# DEVICE.net
KiCad netlist of a schematic drawn in Altium Designer
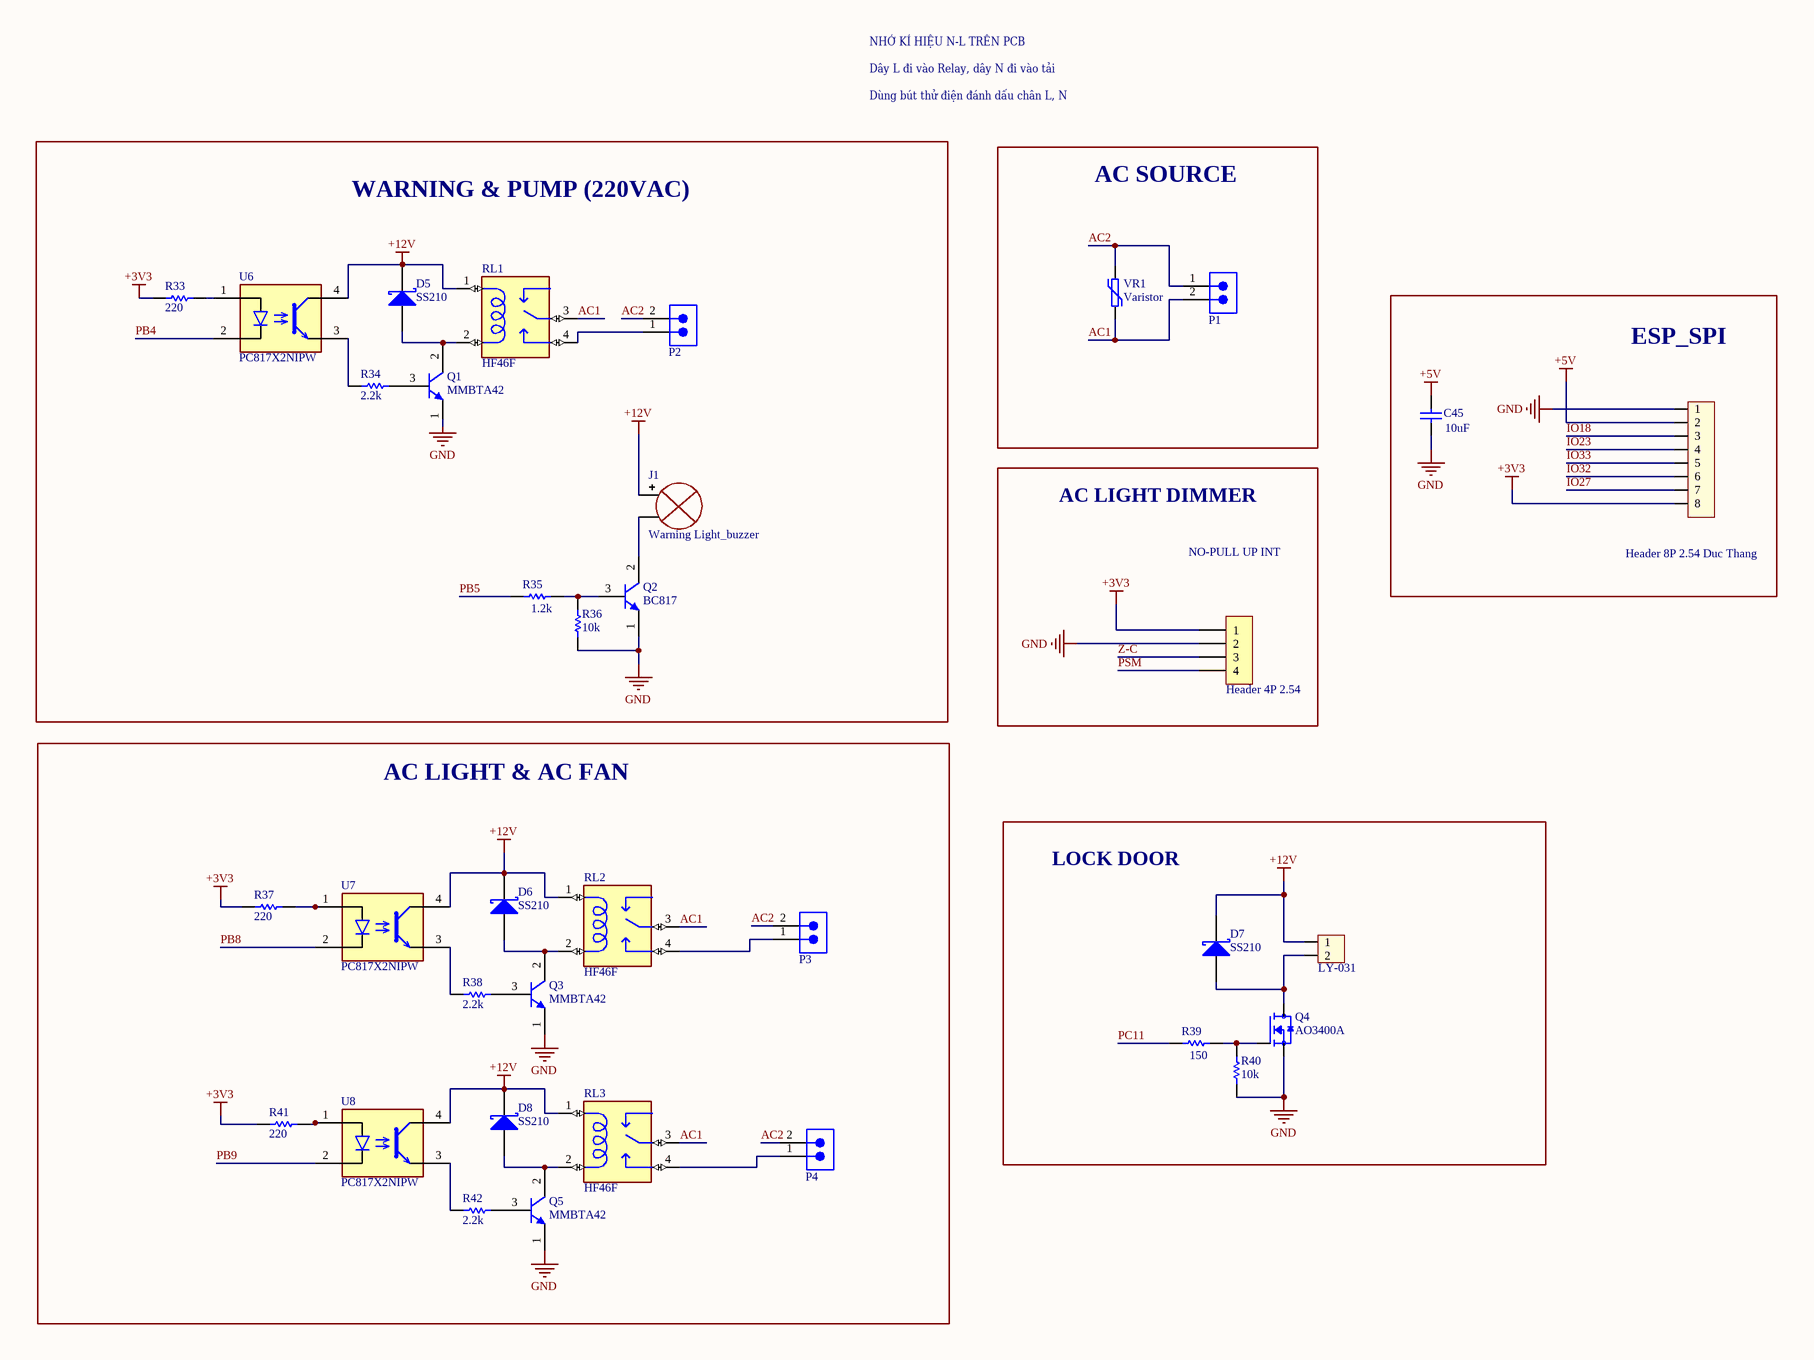
[diagram p0: DEVICE.SchDoc, left]
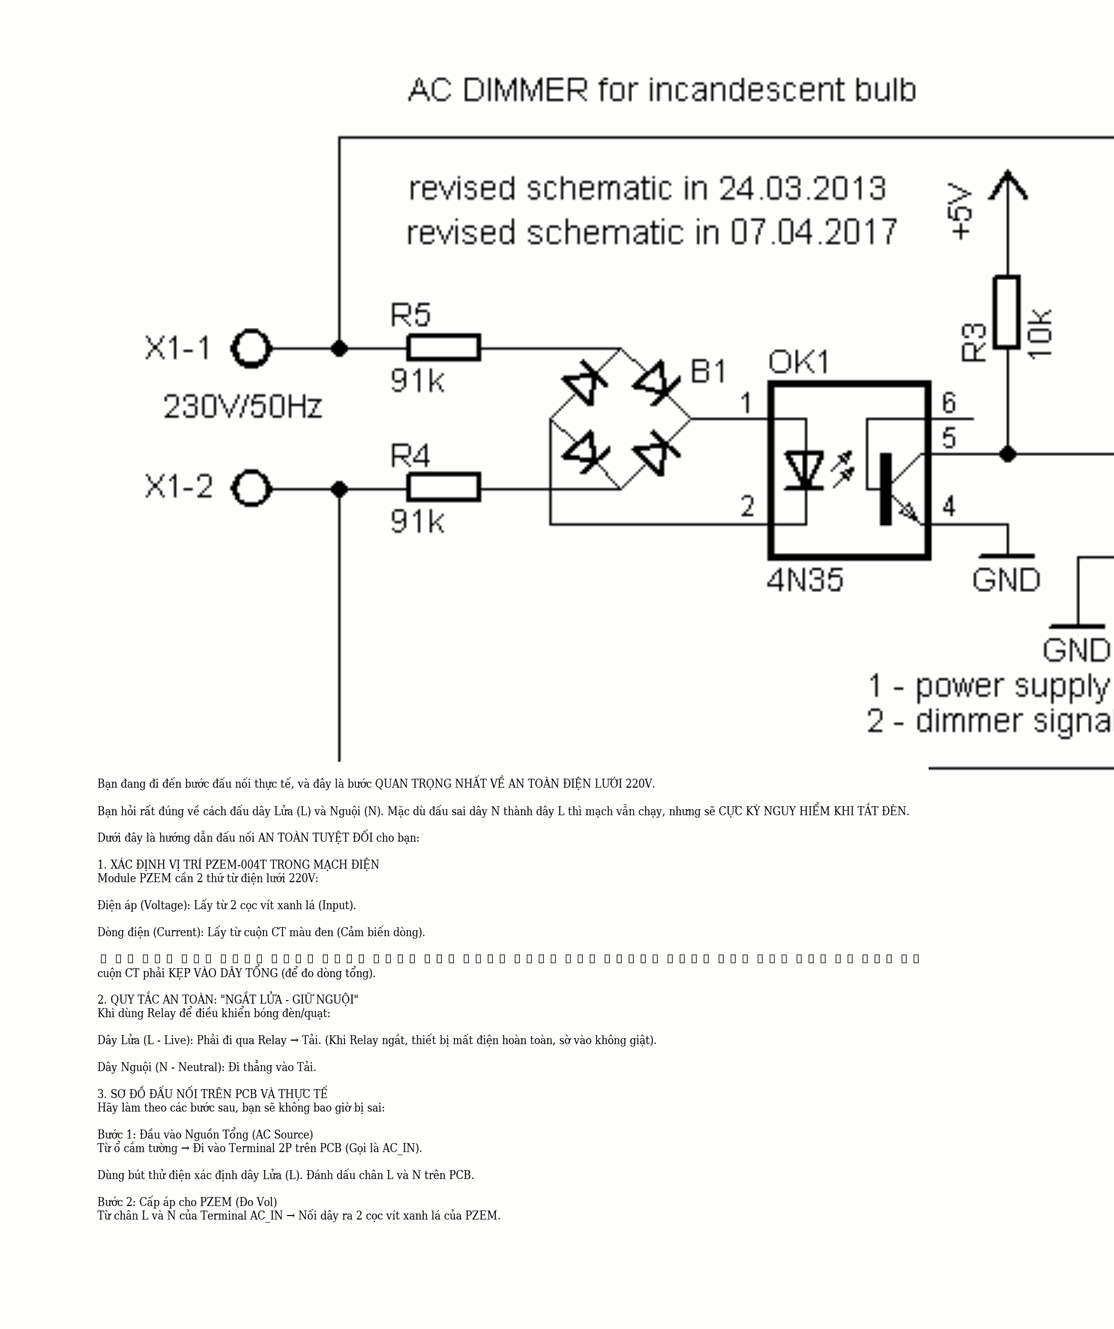
[diagram p1: DEVICE.SchDoc, middle]
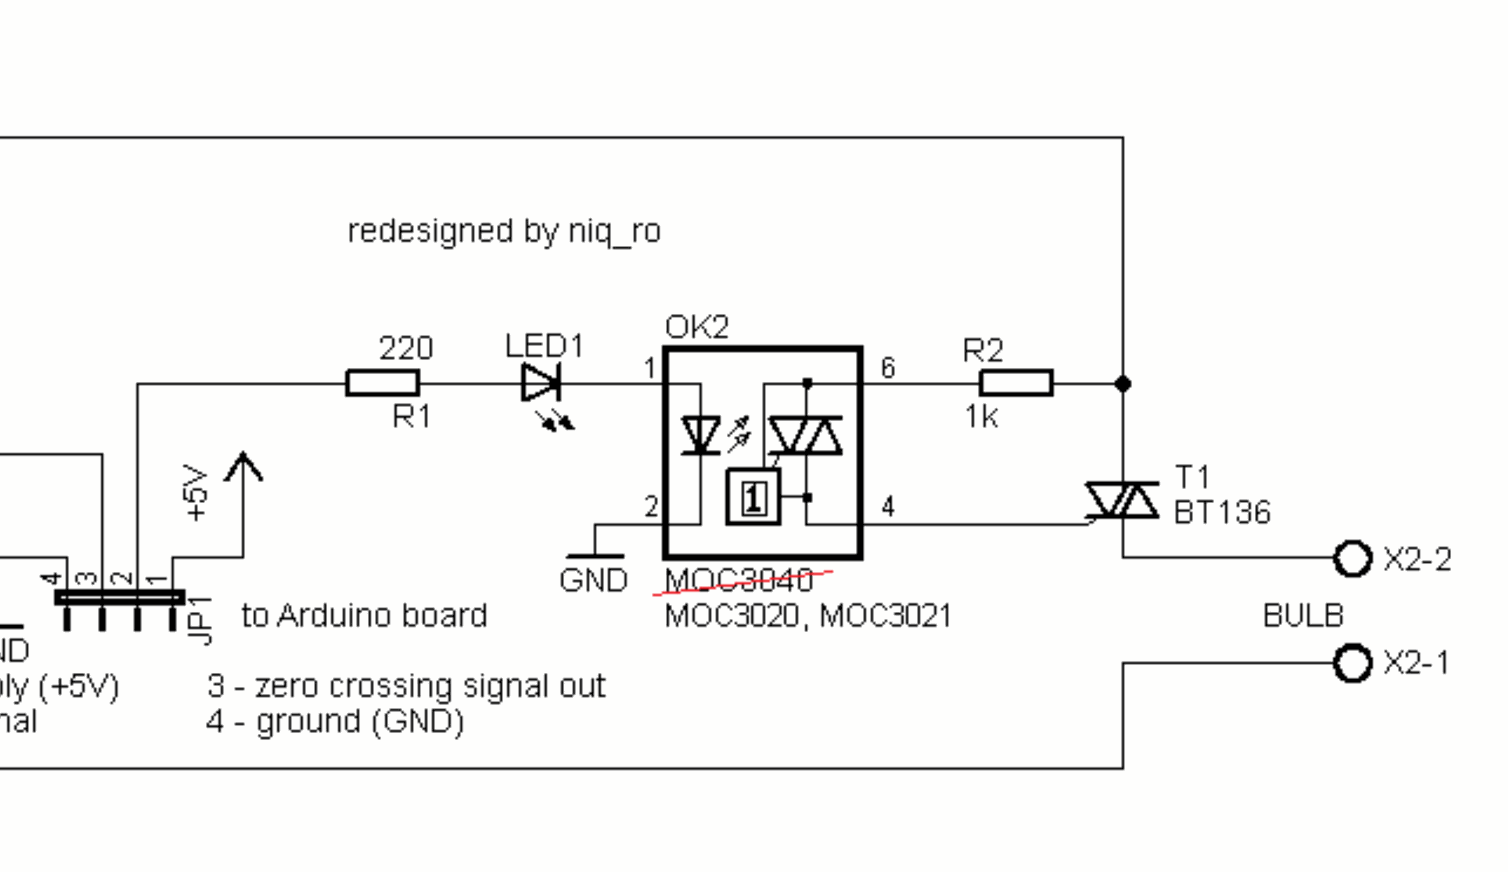
[diagram p2: DEVICE.SchDoc, right]

(export (version "E")
  (design (tool "Eeschema 10.0.6"))
  (components
    (comp (ref "C45")
      (value "10uF")
      (footprint "CAP_0603")
      (description "CAP, size 0603,10uF")
      (libsource (lib "SMIOT_Lib_Schematic") (part "01060310010"))
    )
    (comp (ref "D5")
      (value "SS210")
      (footprint "SS34")
      (description "Schottky Diode")
      (fields (field (name "PUBLISHER") "Altium Limited"))
      (libsource (lib "SMIOT_Lib_Schematic") (part "D Schottky"))
    )
    (comp (ref "D6")
      (value "SS210")
      (footprint "SS34")
      (description "Schottky Diode")
      (fields (field (name "PUBLISHER") "Altium Limited"))
      (libsource (lib "SMIOT_Lib_Schematic") (part "D Schottky"))
    )
    (comp (ref "D7")
      (value "SS210")
      (footprint "SS34")
      (description "Schottky Diode")
      (fields (field (name "PUBLISHER") "Altium Limited"))
      (libsource (lib "SMIOT_Lib_Schematic") (part "D Schottky"))
    )
    (comp (ref "D8")
      (value "SS210")
      (footprint "SS34")
      (description "Schottky Diode")
      (fields (field (name "PUBLISHER") "Altium Limited"))
      (libsource (lib "SMIOT_Lib_Schematic") (part "D Schottky"))
    )
    (comp (ref "H19")
      (value "Header 8P 2.54 Duc Thang")
      (footprint "XH2.54M-8")
      (description "Cắm")
      (libsource (lib "Header") (part "Header 8P 2.54 Duc Thang"))
    )
    (comp (ref "H20")
      (value "Header 4P 2.54")
      (footprint "XH2.54M-4")
      (description "Cắm")
      (libsource (lib "Header") (part "Header 4P 2.54 Duc Thang"))
    )
    (comp (ref "H21")
      (value "LY-031")
      (footprint "XH2.54M-2")
      (description "Cắm")
      (libsource (lib "Header") (part "Header 2P 2.54 Duc Thang"))
    )
    (comp (ref "J1")
      (value "Warning Light_buzzer")
      (footprint "PHOENIX_1935161")
      (libsource (lib "Tironzi") (part "Light_12V"))
    )
    (comp (ref "P1")
      (value "691322310002")
      (footprint "691322310002")
      (description "WR-TBL Series 322 Horizontal PCB Header, THT, pitch 3.81mm, 2p")
      (fields (field (name "MANUFACTURER") "Wurth Elektronik"))
      (libsource (lib "SMIOT_Lib_Schematic") (part "691322310002"))
    )
    (comp (ref "P2")
      (value "691322310002")
      (footprint "691322310002")
      (description "WR-TBL Series 322 Horizontal PCB Header, THT, pitch 3.81mm, 2p")
      (fields (field (name "MANUFACTURER") "Wurth Elektronik"))
      (libsource (lib "SMIOT_Lib_Schematic") (part "691322310002"))
    )
    (comp (ref "P3")
      (value "691322310002")
      (footprint "691322310002")
      (description "WR-TBL Series 322 Horizontal PCB Header, THT, pitch 3.81mm, 2p")
      (fields (field (name "MANUFACTURER") "Wurth Elektronik"))
      (libsource (lib "SMIOT_Lib_Schematic") (part "691322310002"))
    )
    (comp (ref "P4")
      (value "691322310002")
      (footprint "691322310002")
      (description "WR-TBL Series 322 Horizontal PCB Header, THT, pitch 3.81mm, 2p")
      (fields (field (name "MANUFACTURER") "Wurth Elektronik"))
      (libsource (lib "SMIOT_Lib_Schematic") (part "691322310002"))
    )
    (comp (ref "Q1")
      (value "MMBTA42")
      (footprint "SOT23B")
      (description "NPN Bipolar Transistor")
      (libsource (lib "SMIOT_Lib_Schematic") (part "BC817"))
    )
    (comp (ref "Q2")
      (value "BC817")
      (footprint "SOT23B")
      (description "NPN Bipolar Transistor")
      (libsource (lib "SMIOT_Lib_Schematic") (part "BC817"))
    )
    (comp (ref "Q3")
      (value "MMBTA42")
      (footprint "SOT23B")
      (description "NPN Bipolar Transistor")
      (libsource (lib "SMIOT_Lib_Schematic") (part "BC817"))
    )
    (comp (ref "Q4")
      (value "AO3400A")
      (footprint "SOT95P280X125-3N")
      (description "N-Channel 30 V 5.7A (Ta) 1.4W (Ta) Surface Mount SOT-23-3")
      (fields (field (name "MF") "Alpha & Omega Semiconductor"))
      (libsource (lib "AO3400A") (part "AO3400A"))
    )
    (comp (ref "Q5")
      (value "MMBTA42")
      (footprint "SOT23B")
      (description "NPN Bipolar Transistor")
      (libsource (lib "SMIOT_Lib_Schematic") (part "BC817"))
    )
    (comp (ref "R33")
      (value "220")
      (footprint "resistor_0603")
      (description "RES, 220 Ohm, size 0603, 1%")
      (libsource (lib "SMIOT_Lib_Schematic") (part "0006032211"))
    )
    (comp (ref "R34")
      (value "2.2k")
      (footprint "resistor_0603")
      (description "RES, 2.2k Ohm, size 0603, 1%")
      (libsource (lib "SMIOT_Lib_Schematic") (part "0006032221"))
    )
    (comp (ref "R35")
      (value "1.2k")
      (footprint "resistor_0603")
      (description "RES, 1.2k Ohm, size 0603, 1%")
      (libsource (lib "SMIOT_Lib_Schematic") (part "0006032221"))
    )
    (comp (ref "R36")
      (value "10k")
      (footprint "resistor_0603")
      (description "RES, 10k Ohm, size 0603, 1%")
      (libsource (lib "SMIOT_Lib_Schematic") (part "0006032221"))
    )
    (comp (ref "R37")
      (value "220")
      (footprint "resistor_0603")
      (description "RES, 220 Ohm, size 0603, 1%")
      (libsource (lib "SMIOT_Lib_Schematic") (part "0006032211"))
    )
    (comp (ref "R38")
      (value "2.2k")
      (footprint "resistor_0603")
      (description "RES, 2.2k Ohm, size 0603, 1%")
      (libsource (lib "SMIOT_Lib_Schematic") (part "0006032221"))
    )
    (comp (ref "R39")
      (value "150")
      (footprint "resistor_0603")
      (description "RES, 150 Ohm, size 0603, 1%")
      (libsource (lib "SMIOT_Lib_Schematic") (part "0006032221"))
    )
    (comp (ref "R40")
      (value "10k")
      (footprint "resistor_0603")
      (description "RES, 10k Ohm, size 0603, 1%")
      (libsource (lib "SMIOT_Lib_Schematic") (part "0006032221"))
    )
    (comp (ref "R41")
      (value "220")
      (footprint "resistor_0603")
      (description "RES, 220 Ohm, size 0603, 1%")
      (libsource (lib "SMIOT_Lib_Schematic") (part "0006032211"))
    )
    (comp (ref "R42")
      (value "2.2k")
      (footprint "resistor_0603")
      (description "RES, 2.2k Ohm, size 0603, 1%")
      (libsource (lib "SMIOT_Lib_Schematic") (part "0006032221"))
    )
    (comp (ref "RL1")
      (value "HF46F")
      (footprint "HF46F")
      (description "SeriesHF46F 12V 1 Form A 1A Gold Plated SUBMINIATURE INTERMEDIATE POWER RELAY")
      (fields (field (name "MF") "Hongfa"))
      (libsource (lib "SMIOT_Lib_Schematic") (part "HF46F"))
    )
    (comp (ref "RL2")
      (value "HF46F")
      (footprint "HF46F")
      (description "SeriesHF46F 12V 1 Form A 1A Gold Plated SUBMINIATURE INTERMEDIATE POWER RELAY")
      (fields (field (name "MF") "Hongfa"))
      (libsource (lib "SMIOT_Lib_Schematic") (part "HF46F"))
    )
    (comp (ref "RL3")
      (value "HF46F")
      (footprint "HF46F")
      (description "SeriesHF46F 12V 1 Form A 1A Gold Plated SUBMINIATURE INTERMEDIATE POWER RELAY")
      (fields (field (name "MF") "Hongfa"))
      (libsource (lib "SMIOT_Lib_Schematic") (part "HF46F"))
    )
    (comp (ref "U6")
      (value "PC817X2NIPW")
      (footprint "PC817XI_SHP")
      (libsource (lib "SMIOT_Lib_Schematic") (part "PC817X2NIPW"))
    )
    (comp (ref "U7")
      (value "PC817X2NIPW")
      (footprint "PC817XI_SHP")
      (libsource (lib "SMIOT_Lib_Schematic") (part "PC817X2NIPW"))
    )
    (comp (ref "U8")
      (value "PC817X2NIPW")
      (footprint "PC817XI_SHP")
      (libsource (lib "SMIOT_Lib_Schematic") (part "PC817X2NIPW"))
    )
    (comp (ref "VR1")
      (value "Varistor")
      (footprint "07D471K")
      (description "07D471K 470V")
      (libsource (lib "SMIOT_Lib_Schematic") (part "07D471K 470V"))
    )
  )
  (nets
    (net (code "1") (name "+3V3") (class "Default")
      (node (ref "H19") (pin "8") (pinfunction "8_8") (pintype "passive"))
      (node (ref "H20") (pin "1") (pinfunction "1_1") (pintype "passive"))
      (node (ref "R33") (pin "1") (pinfunction "1_1") (pintype "passive"))
      (node (ref "R37") (pin "1") (pinfunction "1_1") (pintype "passive"))
      (node (ref "R41") (pin "1") (pinfunction "1_1") (pintype "passive"))
    )
    (net (code "2") (name "+5V") (class "Default")
      (node (ref "C45") (pin "2") (pinfunction "2_2") (pintype "passive"))
      (node (ref "H19") (pin "2") (pinfunction "2_2") (pintype "passive"))
    )
    (net (code "3") (name "+12V") (class "Default")
      (node (ref "D5") (pin "2") (pinfunction "K_2") (pintype "passive"))
      (node (ref "D6") (pin "2") (pinfunction "K_2") (pintype "passive"))
      (node (ref "D7") (pin "2") (pinfunction "K_2") (pintype "passive"))
      (node (ref "D8") (pin "2") (pinfunction "K_2") (pintype "passive"))
      (node (ref "H21") (pin "1") (pinfunction "1_1") (pintype "passive"))
      (node (ref "J1") (pin "1") (pinfunction "+_1") (pintype "passive"))
      (node (ref "RL1") (pin "1") (pinfunction "C1_1") (pintype "bidirectional"))
      (node (ref "RL2") (pin "1") (pinfunction "C1_1") (pintype "bidirectional"))
      (node (ref "RL3") (pin "1") (pinfunction "C1_1") (pintype "bidirectional"))
      (node (ref "U6") (pin "4") (pinfunction "4_4") (pintype "passive"))
      (node (ref "U7") (pin "4") (pinfunction "4_4") (pintype "passive"))
      (node (ref "U8") (pin "4") (pinfunction "4_4") (pintype "passive"))
    )
    (net (code "4") (name "/AC1") (class "Default")
      (node (ref "P1") (pin "2") (pinfunction "2_2") (pintype "passive"))
      (node (ref "RL1") (pin "3") (pinfunction "C_3") (pintype "bidirectional"))
      (node (ref "RL2") (pin "3") (pinfunction "C_3") (pintype "bidirectional"))
      (node (ref "RL3") (pin "3") (pinfunction "C_3") (pintype "bidirectional"))
      (node (ref "VR1") (pin "2") (pinfunction "2_2") (pintype "passive"))
    )
    (net (code "5") (name "/AC2") (class "Default")
      (node (ref "P1") (pin "1") (pinfunction "1_1") (pintype "passive"))
      (node (ref "P2") (pin "2") (pinfunction "2_2") (pintype "passive"))
      (node (ref "P3") (pin "2") (pinfunction "2_2") (pintype "passive"))
      (node (ref "P4") (pin "2") (pinfunction "2_2") (pintype "passive"))
      (node (ref "VR1") (pin "1") (pinfunction "1_1") (pintype "passive"))
    )
    (net (code "6") (name "/IO18") (class "Default")
      (node (ref "H19") (pin "3") (pinfunction "3_3") (pintype "passive"))
    )
    (net (code "7") (name "/IO23") (class "Default")
      (node (ref "H19") (pin "4") (pinfunction "4_4") (pintype "passive"))
    )
    (net (code "8") (name "/IO27") (class "Default")
      (node (ref "H19") (pin "7") (pinfunction "7_7") (pintype "passive"))
    )
    (net (code "9") (name "/IO32") (class "Default")
      (node (ref "H19") (pin "6") (pinfunction "6_6") (pintype "passive"))
    )
    (net (code "10") (name "/IO33") (class "Default")
      (node (ref "H19") (pin "5") (pinfunction "5_5") (pintype "passive"))
    )
    (net (code "11") (name "/PB4") (class "Default")
      (node (ref "U6") (pin "2") (pinfunction "2_2") (pintype "passive"))
    )
    (net (code "12") (name "/PB5") (class "Default")
      (node (ref "R35") (pin "1") (pinfunction "1_1") (pintype "passive"))
    )
    (net (code "13") (name "/PB8") (class "Default")
      (node (ref "U7") (pin "2") (pinfunction "2_2") (pintype "passive"))
    )
    (net (code "14") (name "/PB9") (class "Default")
      (node (ref "U8") (pin "2") (pinfunction "2_2") (pintype "passive"))
    )
    (net (code "15") (name "/PC11") (class "Default")
      (node (ref "R39") (pin "1") (pinfunction "1_1") (pintype "passive"))
    )
    (net (code "16") (name "/PSM") (class "Default")
      (node (ref "H20") (pin "4") (pinfunction "4_4") (pintype "passive"))
    )
    (net (code "17") (name "/Z-C") (class "Default")
      (node (ref "H20") (pin "3") (pinfunction "3_3") (pintype "passive"))
    )
    (net (code "18") (name "GND") (class "Default")
      (node (ref "C45") (pin "1") (pinfunction "1_1") (pintype "passive"))
      (node (ref "H19") (pin "1") (pinfunction "1_1") (pintype "passive"))
      (node (ref "H20") (pin "2") (pinfunction "2_2") (pintype "passive"))
      (node (ref "Q1") (pin "1") (pinfunction "E_1") (pintype "passive"))
      (node (ref "Q2") (pin "1") (pinfunction "E_1") (pintype "passive"))
      (node (ref "Q3") (pin "1") (pinfunction "E_1") (pintype "passive"))
      (node (ref "Q4") (pin "2") (pinfunction "S_2") (pintype "passive"))
      (node (ref "Q5") (pin "1") (pinfunction "E_1") (pintype "passive"))
      (node (ref "R36") (pin "1") (pinfunction "1_1") (pintype "passive"))
      (node (ref "R40") (pin "1") (pinfunction "1_1") (pintype "passive"))
    )
    (net (code "19") (name "Net-(D5-A)") (class "Default")
      (node (ref "D5") (pin "1") (pinfunction "A_1") (pintype "passive"))
      (node (ref "Q1") (pin "2") (pinfunction "C_2") (pintype "passive"))
      (node (ref "RL1") (pin "2") (pinfunction "C2_2") (pintype "bidirectional"))
    )
    (net (code "20") (name "Net-(D6-A)") (class "Default")
      (node (ref "D6") (pin "1") (pinfunction "A_1") (pintype "passive"))
      (node (ref "Q3") (pin "2") (pinfunction "C_2") (pintype "passive"))
      (node (ref "RL2") (pin "2") (pinfunction "C2_2") (pintype "bidirectional"))
    )
    (net (code "21") (name "Net-(D7-A)") (class "Default")
      (node (ref "D7") (pin "1") (pinfunction "A_1") (pintype "passive"))
      (node (ref "H21") (pin "2") (pinfunction "2_2") (pintype "passive"))
      (node (ref "Q4") (pin "3") (pinfunction "D_3") (pintype "passive"))
    )
    (net (code "22") (name "Net-(D8-A)") (class "Default")
      (node (ref "D8") (pin "1") (pinfunction "A_1") (pintype "passive"))
      (node (ref "Q5") (pin "2") (pinfunction "C_2") (pintype "passive"))
      (node (ref "RL3") (pin "2") (pinfunction "C2_2") (pintype "bidirectional"))
    )
    (net (code "23") (name "Net-(J1--)") (class "Default")
      (node (ref "J1") (pin "2") (pinfunction "-_2") (pintype "passive"))
      (node (ref "Q2") (pin "2") (pinfunction "C_2") (pintype "passive"))
    )
    (net (code "24") (name "Net-(Q1-B)") (class "Default")
      (node (ref "Q1") (pin "3") (pinfunction "B_3") (pintype "passive"))
      (node (ref "R34") (pin "2") (pinfunction "2_2") (pintype "passive"))
    )
    (net (code "25") (name "Net-(Q2-B)") (class "Default")
      (node (ref "Q2") (pin "3") (pinfunction "B_3") (pintype "passive"))
      (node (ref "R35") (pin "2") (pinfunction "2_2") (pintype "passive"))
      (node (ref "R36") (pin "2") (pinfunction "2_2") (pintype "passive"))
    )
    (net (code "26") (name "Net-(Q3-B)") (class "Default")
      (node (ref "Q3") (pin "3") (pinfunction "B_3") (pintype "passive"))
      (node (ref "R38") (pin "2") (pinfunction "2_2") (pintype "passive"))
    )
    (net (code "27") (name "Net-(Q4-G)") (class "Default")
      (node (ref "Q4") (pin "1") (pinfunction "G_1") (pintype "passive"))
      (node (ref "R39") (pin "2") (pinfunction "2_2") (pintype "passive"))
      (node (ref "R40") (pin "2") (pinfunction "2_2") (pintype "passive"))
    )
    (net (code "28") (name "Net-(Q5-B)") (class "Default")
      (node (ref "Q5") (pin "3") (pinfunction "B_3") (pintype "passive"))
      (node (ref "R42") (pin "2") (pinfunction "2_2") (pintype "passive"))
    )
    (net (code "29") (name "Net-(R33-Pad2)") (class "Default")
      (node (ref "R33") (pin "2") (pinfunction "2_2") (pintype "passive"))
      (node (ref "U6") (pin "1") (pinfunction "1_1") (pintype "passive"))
    )
    (net (code "30") (name "Net-(R34-Pad1)") (class "Default")
      (node (ref "R34") (pin "1") (pinfunction "1_1") (pintype "passive"))
      (node (ref "U6") (pin "3") (pinfunction "3_3") (pintype "passive"))
    )
    (net (code "31") (name "Net-(R37-Pad2)") (class "Default")
      (node (ref "R37") (pin "2") (pinfunction "2_2") (pintype "passive"))
      (node (ref "U7") (pin "1") (pinfunction "1_1") (pintype "passive"))
    )
    (net (code "32") (name "Net-(R38-Pad1)") (class "Default")
      (node (ref "R38") (pin "1") (pinfunction "1_1") (pintype "passive"))
      (node (ref "U7") (pin "3") (pinfunction "3_3") (pintype "passive"))
    )
    (net (code "33") (name "Net-(R41-Pad2)") (class "Default")
      (node (ref "R41") (pin "2") (pinfunction "2_2") (pintype "passive"))
      (node (ref "U8") (pin "1") (pinfunction "1_1") (pintype "passive"))
    )
    (net (code "34") (name "Net-(R42-Pad1)") (class "Default")
      (node (ref "R42") (pin "1") (pinfunction "1_1") (pintype "passive"))
      (node (ref "U8") (pin "3") (pinfunction "3_3") (pintype "passive"))
    )
    (net (code "35") (name "Net-(RL1-NO)") (class "Default")
      (node (ref "P2") (pin "1") (pinfunction "1_1") (pintype "passive"))
      (node (ref "RL1") (pin "4") (pinfunction "NO_4") (pintype "bidirectional"))
    )
    (net (code "36") (name "Net-(RL2-NO)") (class "Default")
      (node (ref "P3") (pin "1") (pinfunction "1_1") (pintype "passive"))
      (node (ref "RL2") (pin "4") (pinfunction "NO_4") (pintype "bidirectional"))
    )
    (net (code "37") (name "Net-(RL3-NO)") (class "Default")
      (node (ref "P4") (pin "1") (pinfunction "1_1") (pintype "passive"))
      (node (ref "RL3") (pin "4") (pinfunction "NO_4") (pintype "bidirectional"))
    )
  )
)
